# emonTx_V3_4.net
KiCad netlist of a schematic drawn in EAGLE
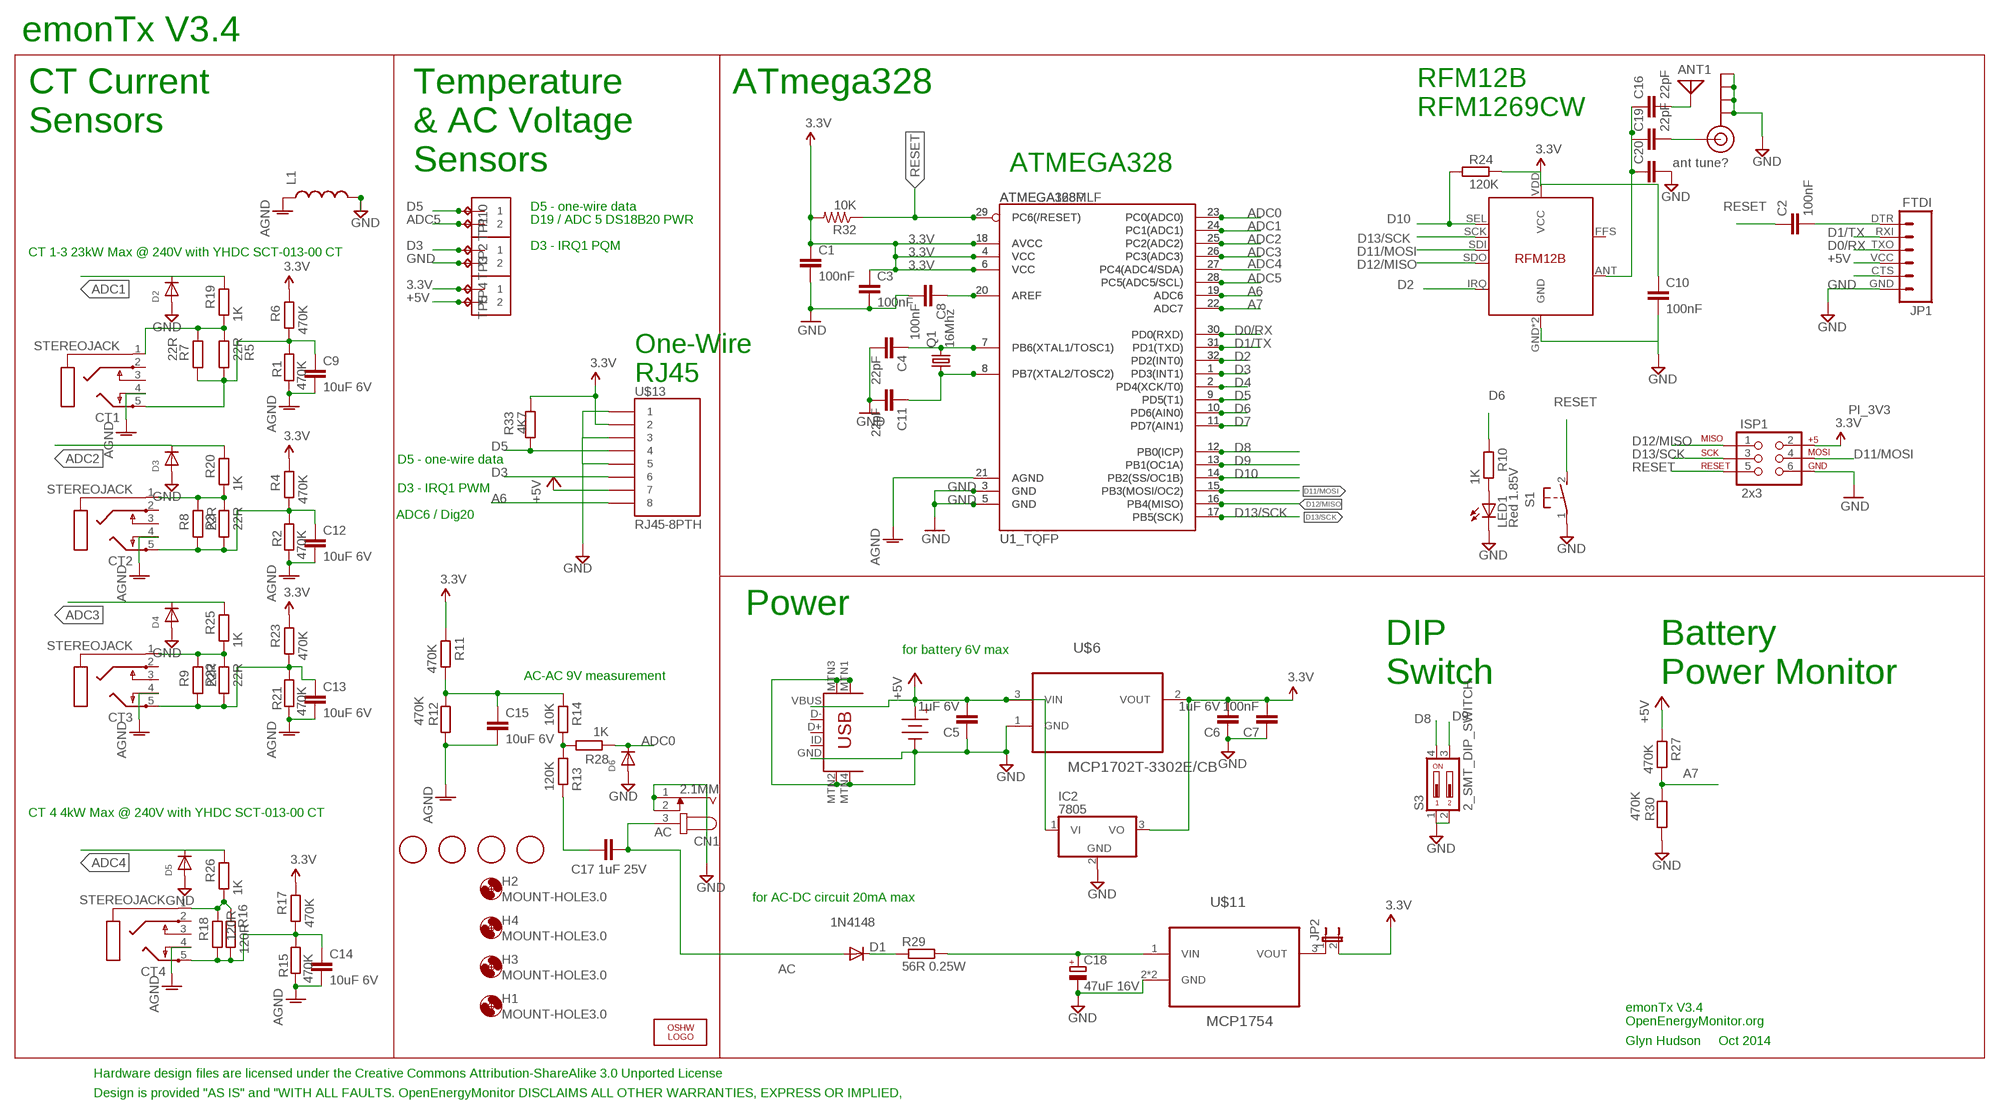
[diagram p0: schematic, sheet 1]

(export (version "E")
  (design (tool "Eeschema 10.0.6"))
  (components
    (comp (ref "ANT1")
      (value "ANTENNA")
      (footprint "eagle-import:PAD-01")
      (libsource (lib "eagle-import") (part "ANTENNA"))
    )
    (comp (ref "C1")
      (value "100nF")
      (footprint "eagle-import:C0603")
      (libsource (lib "eagle-import") (part "C-EUC0603"))
    )
    (comp (ref "C2")
      (value "100nF")
      (footprint "eagle-import:C0603")
      (libsource (lib "eagle-import") (part "C-EUC0603"))
    )
    (comp (ref "C3")
      (value "100nF")
      (footprint "eagle-import:C0603")
      (libsource (lib "eagle-import") (part "resistor_C-EUC0603"))
    )
    (comp (ref "C4")
      (value "22pF")
      (footprint "eagle-import:C0603")
      (libsource (lib "eagle-import") (part "resistor_C-EUC0603"))
    )
    (comp (ref "C5")
      (value "1uF 6V")
      (footprint "eagle-import:C0603")
      (libsource (lib "eagle-import") (part "resistor_C-EUC0603"))
    )
    (comp (ref "C6")
      (value "1uF 6V")
      (footprint "eagle-import:C0603")
      (libsource (lib "eagle-import") (part "resistor_C-EUC0603"))
    )
    (comp (ref "C7")
      (value "100nF")
      (footprint "eagle-import:C0603")
      (libsource (lib "eagle-import") (part "resistor_C-EUC0603"))
    )
    (comp (ref "C8")
      (value "100nF")
      (footprint "eagle-import:C0603")
      (libsource (lib "eagle-import") (part "resistor_C-EUC0603"))
    )
    (comp (ref "C9")
      (value "10uF 6V")
      (footprint "eagle-import:C0603")
      (libsource (lib "eagle-import") (part "resistor_C-EUC0603"))
    )
    (comp (ref "C10")
      (value "100nF")
      (footprint "eagle-import:C0603")
      (libsource (lib "eagle-import") (part "C-EUC0603"))
    )
    (comp (ref "C11")
      (value "22pF")
      (footprint "eagle-import:C0603")
      (libsource (lib "eagle-import") (part "resistor_C-EUC0603"))
    )
    (comp (ref "C12")
      (value "10uF 6V")
      (footprint "eagle-import:C0603")
      (libsource (lib "eagle-import") (part "resistor_C-EUC0603"))
    )
    (comp (ref "C13")
      (value "10uF 6V")
      (footprint "eagle-import:C0603")
      (libsource (lib "eagle-import") (part "resistor_C-EUC0603"))
    )
    (comp (ref "C14")
      (value "10uF 6V")
      (footprint "eagle-import:C0603")
      (libsource (lib "eagle-import") (part "resistor_C-EUC0603"))
    )
    (comp (ref "C15")
      (value "10uF 6V")
      (footprint "eagle-import:C0603")
      (libsource (lib "eagle-import") (part "resistor_C-EUC0603"))
    )
    (comp (ref "C16")
      (value "22pF")
      (footprint "eagle-import:C0603")
      (libsource (lib "eagle-import") (part "C-EUC0603"))
    )
    (comp (ref "C17")
      (value "1uF 25V")
      (footprint "eagle-import:C0603")
      (libsource (lib "eagle-import") (part "resistor_C-EUC0603"))
    )
    (comp (ref "C18")
      (value "47uF 16V")
      (footprint "eagle-import:PANASONIC_D")
      (libsource (lib "eagle-import") (part "CPOL-EUD"))
    )
    (comp (ref "C19")
      (value "22pF")
      (footprint "eagle-import:C0603")
      (libsource (lib "eagle-import") (part "C-EUC0603"))
    )
    (comp (ref "C20")
      (value "ant tune?")
      (footprint "eagle-import:C0603")
      (libsource (lib "eagle-import") (part "C-EUC0603"))
    )
    (comp (ref "CN1")
      (value "2.1MM")
      (footprint "eagle-import:SPC4077")
      (libsource (lib "eagle-import") (part "JACK-PLUG0"))
    )
    (comp (ref "CT1")
      (value "STEREOJACK")
      (footprint "eagle-import:STX3100")
      (libsource (lib "eagle-import") (part "STEREOJACK"))
    )
    (comp (ref "CT2")
      (value "STEREOJACK")
      (footprint "eagle-import:STX3100")
      (libsource (lib "eagle-import") (part "STEREOJACK"))
    )
    (comp (ref "CT3")
      (value "STEREOJACK")
      (footprint "eagle-import:STX3100")
      (libsource (lib "eagle-import") (part "STEREOJACK"))
    )
    (comp (ref "CT4")
      (value "STEREOJACK")
      (footprint "eagle-import:STX3100")
      (libsource (lib "eagle-import") (part "STEREOJACK"))
    )
    (comp (ref "D1")
      (value "1N4148")
      (footprint "eagle-import:SOD-323")
      (libsource (lib "eagle-import") (part "DIODESOD"))
    )
    (comp (ref "D2")
      (value "DIODESOD-523")
      (footprint "eagle-import:SOD-523")
      (libsource (lib "eagle-import") (part "DIODESOD-523"))
    )
    (comp (ref "D3")
      (value "DIODESOD-523")
      (footprint "eagle-import:SOD-523")
      (libsource (lib "eagle-import") (part "DIODESOD-523"))
    )
    (comp (ref "D4")
      (value "DIODESOD-523")
      (footprint "eagle-import:SOD-523")
      (libsource (lib "eagle-import") (part "DIODESOD-523"))
    )
    (comp (ref "D5")
      (value "DIODESOD-523")
      (footprint "eagle-import:SOD-523")
      (libsource (lib "eagle-import") (part "DIODESOD-523"))
    )
    (comp (ref "D6")
      (value "DIODESOD-523")
      (footprint "eagle-import:SOD-523")
      (libsource (lib "eagle-import") (part "DIODESOD-523"))
    )
    (comp (ref "H1")
      (value "MOUNT-HOLE3.0")
      (footprint "eagle-import:3,0")
      (libsource (lib "eagle-import") (part "MOUNT-HOLE3.0"))
    )
    (comp (ref "H2")
      (value "MOUNT-HOLE3.0")
      (footprint "eagle-import:3,0")
      (libsource (lib "eagle-import") (part "MOUNT-HOLE3.0"))
    )
    (comp (ref "H3")
      (value "MOUNT-HOLE3.0")
      (footprint "eagle-import:3,0")
      (libsource (lib "eagle-import") (part "MOUNT-HOLE3.0"))
    )
    (comp (ref "H4")
      (value "MOUNT-HOLE3.0")
      (footprint "eagle-import:3,0")
      (libsource (lib "eagle-import") (part "MOUNT-HOLE3.0"))
    )
    (comp (ref "IC2")
      (value "7805")
      (footprint "eagle-import:TO220V")
      (libsource (lib "eagle-import") (part "78TV12"))
    )
    (comp (ref "ISP1")
      (value "2x3")
      (footprint "eagle-import:2X3")
      (libsource (lib "eagle-import") (part "AVR_SPI_PRG_6PTH"))
    )
    (comp (ref "J$1")
      (value "SMA_EDGE")
      (footprint "eagle-import:SMA-EDGE")
      (libsource (lib "eagle-import") (part "SMA_EDGE"))
    )
    (comp (ref "J3")
      (value "1X2-3.5MM")
      (footprint "eagle-import:1X2-3.5MM")
      (libsource (lib "eagle-import") (part "1X2-3.5MM"))
    )
    (comp (ref "J5")
      (value "1X2-3.5MM")
      (footprint "eagle-import:1X2-3.5MM")
      (libsource (lib "eagle-import") (part "1X2-3.5MM"))
    )
    (comp (ref "J6")
      (value "1X2-3.5MM")
      (footprint "eagle-import:1X2-3.5MM")
      (libsource (lib "eagle-import") (part "1X2-3.5MM"))
    )
    (comp (ref "JP1")
      (value "FTDI")
      (footprint "eagle-import:FTDI_BASIC")
      (libsource (lib "eagle-import") (part "FTDI_BASICPTH"))
    )
    (comp (ref "JP2")
      (value "JUMPER-2PTH_LOCK")
      (footprint "eagle-import:1X02_LOCK")
      (libsource (lib "eagle-import") (part "JUMPER-2PTH_LOCK"))
    )
    (comp (ref "L1")
      (value "INDUCTOR0603")
      (footprint "eagle-import:0603")
      (libsource (lib "eagle-import") (part "INDUCTOR0603"))
    )
    (comp (ref "LED1")
      (value "Red 1.85V")
      (footprint "eagle-import:CHIP-LED0805")
      (libsource (lib "eagle-import") (part "LEDCHIP-LED0805"))
    )
    (comp (ref "LOGO1")
      (value "OSHW_LOGO_6MILX0200-NT")
      (footprint "eagle-import:OSHW_6X200_NOTEXT")
      (libsource (lib "eagle-import") (part "OSHW_LOGO_6MILX0200-NT"))
    )
    (comp (ref "Q1")
      (value "16Mhz")
      (footprint "eagle-import:HC49UP")
      (libsource (lib "eagle-import") (part "CRYSTALHC49UP"))
    )
    (comp (ref "R1")
      (value "470K")
      (footprint "eagle-import:R0603")
      (libsource (lib "eagle-import") (part "R-EU_R0603"))
    )
    (comp (ref "R2")
      (value "470K")
      (footprint "eagle-import:R0603")
      (libsource (lib "eagle-import") (part "R-EU_R0603"))
    )
    (comp (ref "R3")
      (value "22R")
      (footprint "eagle-import:0204_7")
      (libsource (lib "eagle-import") (part "R-EU_0204/7"))
    )
    (comp (ref "R4")
      (value "470K")
      (footprint "eagle-import:R0603")
      (libsource (lib "eagle-import") (part "R-EU_R0603"))
    )
    (comp (ref "R5")
      (value "22R")
      (footprint "eagle-import:0204_7")
      (libsource (lib "eagle-import") (part "R-EU_0204/7"))
    )
    (comp (ref "R6")
      (value "470K")
      (footprint "eagle-import:R0603")
      (libsource (lib "eagle-import") (part "R-EU_R0603"))
    )
    (comp (ref "R7")
      (value "22R")
      (footprint "eagle-import:R1206")
      (libsource (lib "eagle-import") (part "R-EU_R1206"))
    )
    (comp (ref "R8")
      (value "22R")
      (footprint "eagle-import:R1206")
      (libsource (lib "eagle-import") (part "R-EU_R1206"))
    )
    (comp (ref "R9")
      (value "22R")
      (footprint "eagle-import:R1206")
      (libsource (lib "eagle-import") (part "R-EU_R1206"))
    )
    (comp (ref "R10")
      (value "1K")
      (footprint "eagle-import:R0603")
      (libsource (lib "eagle-import") (part "R-EU_R0603"))
    )
    (comp (ref "R11")
      (value "470K")
      (footprint "eagle-import:R0603")
      (libsource (lib "eagle-import") (part "R-EU_R0603"))
    )
    (comp (ref "R12")
      (value "470K")
      (footprint "eagle-import:R0603")
      (libsource (lib "eagle-import") (part "R-EU_R0603"))
    )
    (comp (ref "R13")
      (value "120K")
      (footprint "eagle-import:R0603")
      (libsource (lib "eagle-import") (part "R-EU_R0603"))
    )
    (comp (ref "R14")
      (value "10K")
      (footprint "eagle-import:R0603")
      (libsource (lib "eagle-import") (part "R-EU_R0603"))
    )
    (comp (ref "R15")
      (value "470K")
      (footprint "eagle-import:R0603")
      (libsource (lib "eagle-import") (part "R-EU_R0603"))
    )
    (comp (ref "R16")
      (value "120R")
      (footprint "eagle-import:0204_7")
      (libsource (lib "eagle-import") (part "R-EU_0204/7"))
    )
    (comp (ref "R17")
      (value "470K")
      (footprint "eagle-import:R0603")
      (libsource (lib "eagle-import") (part "R-EU_R0603"))
    )
    (comp (ref "R18")
      (value "120R")
      (footprint "eagle-import:R1206")
      (libsource (lib "eagle-import") (part "R-EU_R1206"))
    )
    (comp (ref "R19")
      (value "1K")
      (footprint "eagle-import:R0603")
      (libsource (lib "eagle-import") (part "R-EU_R0603"))
    )
    (comp (ref "R20")
      (value "1K")
      (footprint "eagle-import:R0603")
      (libsource (lib "eagle-import") (part "R-EU_R0603"))
    )
    (comp (ref "R21")
      (value "470K")
      (footprint "eagle-import:R0603")
      (libsource (lib "eagle-import") (part "R-EU_R0603"))
    )
    (comp (ref "R22")
      (value "22R")
      (footprint "eagle-import:0204_7")
      (libsource (lib "eagle-import") (part "R-EU_0204/7"))
    )
    (comp (ref "R23")
      (value "470K")
      (footprint "eagle-import:R0603")
      (libsource (lib "eagle-import") (part "R-EU_R0603"))
    )
    (comp (ref "R24")
      (value "120K")
      (footprint "eagle-import:R0603")
      (libsource (lib "eagle-import") (part "R-EU_R0603"))
    )
    (comp (ref "R25")
      (value "1K")
      (footprint "eagle-import:R0603")
      (libsource (lib "eagle-import") (part "R-EU_R0603"))
    )
    (comp (ref "R26")
      (value "1K")
      (footprint "eagle-import:R0603")
      (libsource (lib "eagle-import") (part "R-EU_R0603"))
    )
    (comp (ref "R27")
      (value "470K")
      (footprint "eagle-import:R0603")
      (libsource (lib "eagle-import") (part "R-EU_R0603"))
    )
    (comp (ref "R28")
      (value "1K")
      (footprint "eagle-import:R0603")
      (libsource (lib "eagle-import") (part "R-EU_R0603"))
    )
    (comp (ref "R29")
      (value "56R 0.25W")
      (footprint "eagle-import:R1206")
      (libsource (lib "eagle-import") (part "resistor_R-EU_R1206"))
    )
    (comp (ref "R30")
      (value "470K")
      (footprint "eagle-import:R0603")
      (libsource (lib "eagle-import") (part "R-EU_R0603"))
    )
    (comp (ref "R32")
      (value "10K")
      (footprint "eagle-import:R0603")
      (libsource (lib "eagle-import") (part "R-US_R0603"))
    )
    (comp (ref "R33")
      (value "4K7")
      (footprint "eagle-import:R0603")
      (libsource (lib "eagle-import") (part "R-EU_R0603"))
    )
    (comp (ref "S1")
      (value "31-XX")
      (footprint "eagle-import:B3F-31XX")
      (libsource (lib "eagle-import") (part "31-XX"))
    )
    (comp (ref "S3")
      (value "2_SMT_DIP_SWITCH")
      (footprint "eagle-import:DIP_SWITCH_SMT")
      (libsource (lib "eagle-import") (part "2_SMT_DIP_SWITCH"))
    )
    (comp (ref "TP1")
      (value "TPPAD1-13")
      (footprint "eagle-import:P1-13")
      (libsource (lib "eagle-import") (part "TPPAD1-13"))
    )
    (comp (ref "TP2")
      (value "TPPAD1-13")
      (footprint "eagle-import:P1-13")
      (libsource (lib "eagle-import") (part "TPPAD1-13"))
    )
    (comp (ref "TP3")
      (value "TPPAD1-13")
      (footprint "eagle-import:P1-13")
      (libsource (lib "eagle-import") (part "TPPAD1-13"))
    )
    (comp (ref "TP4")
      (value "TPPAD1-13")
      (footprint "eagle-import:P1-13")
      (libsource (lib "eagle-import") (part "TPPAD1-13"))
    )
    (comp (ref "TP5")
      (value "TPPAD1-13")
      (footprint "eagle-import:P1-13")
      (libsource (lib "eagle-import") (part "TPPAD1-13"))
    )
    (comp (ref "TP10")
      (value "TPPAD1-13")
      (footprint "eagle-import:P1-13")
      (libsource (lib "eagle-import") (part "TPPAD1-13"))
    )
    (comp (ref "U$1")
      (value "FIDUCIAL")
      (footprint "eagle-import:FIDUCIAL_1MM")
      (libsource (lib "eagle-import") (part "FIDUCIAL"))
    )
    (comp (ref "U$3")
      (value "4.5V")
      (footprint "eagle-import:AAA_PCB_HOLDER")
      (libsource (lib "eagle-import") (part "3X_AAA_BATTERY_HOLDER"))
    )
    (comp (ref "U$4")
      (value "FIDUCIAL")
      (footprint "eagle-import:FIDUCIAL_1MM")
      (libsource (lib "eagle-import") (part "FIDUCIAL"))
    )
    (comp (ref "U$5")
      (value "FIDUCIAL")
      (footprint "eagle-import:FIDUCIAL_1MM")
      (libsource (lib "eagle-import") (part "FIDUCIAL"))
    )
    (comp (ref "U$6")
      (value "MCP1702T-3302E/CB")
      (footprint "eagle-import:SOT95P237X112-3N")
      (fields (field (name "MPN") "MCP1700T-3302E/TT"))
      (libsource (lib "eagle-import") (part "MCP1700T-3302E/TT"))
    )
    (comp (ref "U$7")
      (value "FIDUCIAL")
      (footprint "eagle-import:FIDUCIAL_1MM")
      (libsource (lib "eagle-import") (part "FIDUCIAL"))
    )
    (comp (ref "U$10")
      (value "USB-MINIB-5PIN")
      (footprint "eagle-import:USB-MINIB-CISECO")
      (libsource (lib "eagle-import") (part "USB-MINIB-5PIN"))
    )
    (comp (ref "U$11")
      (value "MCP1754")
      (footprint "eagle-import:SOT89")
      (libsource (lib "eagle-import") (part "MCP1754"))
    )
    (comp (ref "U$13")
      (value "RJ45-8PTH")
      (footprint "eagle-import:RJ45-8")
      (libsource (lib "eagle-import") (part "RJ45-8PTH"))
    )
    (comp (ref "U$14")
      (value "RFM12B")
      (footprint "eagle-import:RFM12B")
      (libsource (lib "eagle-import") (part "RFM12B"))
    )
    (comp (ref "U1")
      (value "ATMEGA168MLF")
      (footprint "eagle-import:MLF32")
      (libsource (lib "eagle-import") (part "ATMEGA168MLF"))
    )
    (comp (ref "U1_TQFP")
      (value "ATMEGA328P")
      (footprint "eagle-import:TQFP32-08")
      (libsource (lib "eagle-import") (part "ATMEGA328_SMT"))
    )
  )
  (nets
    (net (code "1") (name "+5V") (class "Default")
      (node (ref "C5") (pin "2") (pinfunction "2_2") (pintype "passive"))
      (node (ref "IC2") (pin "1") (pinfunction "VI_1") (pintype "input"))
      (node (ref "J6") (pin "2") (pinfunction "2_2") (pintype "passive"))
      (node (ref "JP1") (pin "VCC") (pinfunction "4_VCC") (pintype "passive"))
      (node (ref "R27") (pin "2") (pinfunction "2_2") (pintype "passive"))
      (node (ref "TP5") (pin "TP") (pinfunction "TP_TP") (pintype "input"))
      (node (ref "U$10") (pin "VBUS") (pinfunction "VBUS_VBUS") (pintype "bidirectional"))
      (node (ref "U$13") (pin "7") (pinfunction "7_7") (pintype "bidirectional"))
      (node (ref "U$3") (pin "+") (pinfunction "+_+") (pintype "power_in"))
      (node (ref "U$6") (pin "3") (pinfunction "VIN_3") (pintype "input"))
    )
    (net (code "2") (name "/A6") (class "Default")
      (node (ref "U$13") (pin "8") (pinfunction "8_8") (pintype "bidirectional"))
      (node (ref "U1") (pin "19") (pinfunction "ADC6_19") (pintype "bidirectional"))
      (node (ref "U1_TQFP") (pin "19") (pinfunction "ADC6_19") (pintype "bidirectional"))
    )
    (net (code "3") (name "/A7") (class "Default")
      (node (ref "R27") (pin "1") (pinfunction "1_1") (pintype "passive"))
      (node (ref "R30") (pin "2") (pinfunction "2_2") (pintype "passive"))
      (node (ref "U1") (pin "22") (pinfunction "ADC7_22") (pintype "bidirectional"))
      (node (ref "U1_TQFP") (pin "22") (pinfunction "ADC7_22") (pintype "bidirectional"))
    )
    (net (code "4") (name "/AC") (class "Default")
      (node (ref "C17") (pin "2") (pinfunction "2_2") (pintype "passive"))
      (node (ref "CN1") (pin "3") (pinfunction "3_3") (pintype "passive"))
      (node (ref "D1") (pin "2") (pinfunction "A_2") (pintype "passive"))
    )
    (net (code "5") (name "/ADC0") (class "Default")
      (node (ref "D6") (pin "K") (pinfunction "C_K") (pintype "passive"))
      (node (ref "R28") (pin "1") (pinfunction "1_1") (pintype "passive"))
      (node (ref "U1") (pin "23") (pinfunction "PC0(ADC0)_23") (pintype "bidirectional"))
      (node (ref "U1_TQFP") (pin "23") (pinfunction "PC0(ADC0)_23") (pintype "bidirectional"))
    )
    (net (code "6") (name "/ADC5") (class "Default")
      (node (ref "J3") (pin "2") (pinfunction "2_2") (pintype "passive"))
      (node (ref "TP1") (pin "TP") (pinfunction "TP_TP") (pintype "input"))
      (node (ref "U1") (pin "28") (pinfunction "PC5(ADC5/SCL)_28") (pintype "bidirectional"))
      (node (ref "U1_TQFP") (pin "28") (pinfunction "PC5(ADC5/SCL)_28") (pintype "bidirectional"))
    )
    (net (code "7") (name "/D0{slash}RX") (class "Default")
      (node (ref "JP1") (pin "TXO") (pinfunction "3_TXO") (pintype "passive"))
      (node (ref "U1") (pin "30") (pinfunction "PD0(RXD)_30") (pintype "bidirectional"))
      (node (ref "U1_TQFP") (pin "30") (pinfunction "PD0(RXD)_30") (pintype "bidirectional"))
    )
    (net (code "8") (name "/D1{slash}TX") (class "Default")
      (node (ref "JP1") (pin "RXI") (pinfunction "2_RXI") (pintype "passive"))
      (node (ref "U1") (pin "31") (pinfunction "PD1(TXD)_31") (pintype "bidirectional"))
      (node (ref "U1_TQFP") (pin "31") (pinfunction "PD1(TXD)_31") (pintype "bidirectional"))
    )
    (net (code "9") (name "/D2") (class "Default")
      (node (ref "U$14") (pin "IRQ") (pinfunction "IRQ_IRQ") (pintype "open_collector"))
      (node (ref "U1") (pin "32") (pinfunction "PD2(INT0)_32") (pintype "bidirectional"))
      (node (ref "U1_TQFP") (pin "32") (pinfunction "PD2(INT0)_32") (pintype "bidirectional"))
    )
    (net (code "10") (name "/D3") (class "Default")
      (node (ref "J5") (pin "1") (pinfunction "1_1") (pintype "passive"))
      (node (ref "TP2") (pin "TP") (pinfunction "TP_TP") (pintype "input"))
      (node (ref "U$13") (pin "6") (pinfunction "6_6") (pintype "bidirectional"))
      (node (ref "U1") (pin "1") (pinfunction "PD3(INT1)_1") (pintype "bidirectional"))
      (node (ref "U1_TQFP") (pin "1") (pinfunction "PD3(INT1)_1") (pintype "bidirectional"))
    )
    (net (code "11") (name "/D4") (class "Default")
      (node (ref "U1") (pin "2") (pinfunction "PD4(XCK/T0)_2") (pintype "bidirectional"))
      (node (ref "U1_TQFP") (pin "2") (pinfunction "PD4(XCK/T0)_2") (pintype "bidirectional"))
    )
    (net (code "12") (name "/D5") (class "Default")
      (node (ref "J3") (pin "1") (pinfunction "1_1") (pintype "passive"))
      (node (ref "R33") (pin "2") (pinfunction "2_2") (pintype "passive"))
      (node (ref "TP10") (pin "TP") (pinfunction "TP_TP") (pintype "input"))
      (node (ref "U$13") (pin "4") (pinfunction "4_4") (pintype "bidirectional"))
      (node (ref "U1") (pin "9") (pinfunction "PD5(T1)_9") (pintype "bidirectional"))
      (node (ref "U1_TQFP") (pin "9") (pinfunction "PD5(T1)_9") (pintype "bidirectional"))
    )
    (net (code "13") (name "/D6") (class "Default")
      (node (ref "R10") (pin "2") (pinfunction "2_2") (pintype "passive"))
      (node (ref "U1") (pin "10") (pinfunction "PD6(AIN0)_10") (pintype "bidirectional"))
      (node (ref "U1_TQFP") (pin "10") (pinfunction "PD6(AIN0)_10") (pintype "bidirectional"))
    )
    (net (code "14") (name "/D7") (class "Default")
      (node (ref "U1") (pin "11") (pinfunction "PD7(AIN1)_11") (pintype "bidirectional"))
      (node (ref "U1_TQFP") (pin "11") (pinfunction "PD7(AIN1)_11") (pintype "bidirectional"))
    )
    (net (code "15") (name "/D8") (class "Default")
      (node (ref "S3") (pin "4") (pinfunction "4_4") (pintype "passive"))
      (node (ref "U1") (pin "12") (pinfunction "PB0(ICP)_12") (pintype "bidirectional"))
      (node (ref "U1_TQFP") (pin "12") (pinfunction "PB0(ICP)_12") (pintype "bidirectional"))
    )
    (net (code "16") (name "/D9") (class "Default")
      (node (ref "S3") (pin "3") (pinfunction "3_3") (pintype "passive"))
      (node (ref "U1") (pin "13") (pinfunction "PB1(OC1A)_13") (pintype "bidirectional"))
      (node (ref "U1_TQFP") (pin "13") (pinfunction "PB1(OC1A)_13") (pintype "bidirectional"))
    )
    (net (code "17") (name "/D10") (class "Default")
      (node (ref "R24") (pin "1") (pinfunction "1_1") (pintype "passive"))
      (node (ref "U$14") (pin "SEL") (pinfunction "SEL_SEL") (pintype "input"))
      (node (ref "U1") (pin "14") (pinfunction "PB2(SS/OC1B)_14") (pintype "bidirectional"))
      (node (ref "U1_TQFP") (pin "14") (pinfunction "PB2(SS/OC1B)_14") (pintype "bidirectional"))
    )
    (net (code "19") (name "3.3V") (class "Default")
      (node (ref "C1") (pin "1") (pinfunction "1_1") (pintype "passive"))
      (node (ref "C10") (pin "1") (pinfunction "1_1") (pintype "passive"))
      (node (ref "C3") (pin "1") (pinfunction "1_1") (pintype "passive"))
      (node (ref "C6") (pin "2") (pinfunction "2_2") (pintype "passive"))
      (node (ref "C7") (pin "2") (pinfunction "2_2") (pintype "passive"))
      (node (ref "IC2") (pin "3") (pinfunction "VO_3") (pintype "passive"))
      (node (ref "ISP1") (pin "2") (pinfunction "2_2") (pintype "passive"))
      (node (ref "J6") (pin "1") (pinfunction "1_1") (pintype "passive"))
      (node (ref "JP2") (pin "2") (pinfunction "2_2") (pintype "passive"))
      (node (ref "R11") (pin "2") (pinfunction "2_2") (pintype "passive"))
      (node (ref "R17") (pin "2") (pinfunction "2_2") (pintype "passive"))
      (node (ref "R23") (pin "2") (pinfunction "2_2") (pintype "passive"))
      (node (ref "R24") (pin "2") (pinfunction "2_2") (pintype "passive"))
      (node (ref "R32") (pin "2") (pinfunction "2_2") (pintype "passive"))
      (node (ref "R33") (pin "1") (pinfunction "1_1") (pintype "passive"))
      (node (ref "R4") (pin "2") (pinfunction "2_2") (pintype "passive"))
      (node (ref "R6") (pin "2") (pinfunction "2_2") (pintype "passive"))
      (node (ref "TP4") (pin "TP") (pinfunction "TP_TP") (pintype "input"))
      (node (ref "U$13") (pin "2") (pinfunction "2_2") (pintype "bidirectional"))
      (node (ref "U$14") (pin "VDD") (pinfunction "VCC_VDD") (pintype "power_in"))
      (node (ref "U$6") (pin "2") (pinfunction "VOUT_2") (pintype "output"))
      (node (ref "U1") (pin "18") (pinfunction "AVCC_18") (pintype "bidirectional"))
      (node (ref "U1") (pin "4") (pinfunction "VCC_4") (pintype "bidirectional"))
      (node (ref "U1") (pin "6") (pinfunction "VCC_6") (pintype "bidirectional"))
      (node (ref "U1_TQFP") (pin "18") (pinfunction "AVCC_18") (pintype "bidirectional"))
      (node (ref "U1_TQFP") (pin "4") (pinfunction "VCC_4") (pintype "bidirectional"))
      (node (ref "U1_TQFP") (pin "6") (pinfunction "VCC_6") (pintype "bidirectional"))
    )
    (net (code "20") (name "ADC1") (class "Default")
      (node (ref "D2") (pin "K") (pinfunction "C_K") (pintype "passive"))
      (node (ref "R19") (pin "2") (pinfunction "2_2") (pintype "passive"))
      (node (ref "U1") (pin "24") (pinfunction "PC1(ADC1)_24") (pintype "bidirectional"))
      (node (ref "U1_TQFP") (pin "24") (pinfunction "PC1(ADC1)_24") (pintype "bidirectional"))
    )
    (net (code "21") (name "ADC2") (class "Default")
      (node (ref "D3") (pin "K") (pinfunction "C_K") (pintype "passive"))
      (node (ref "R20") (pin "2") (pinfunction "2_2") (pintype "passive"))
      (node (ref "U1") (pin "25") (pinfunction "PC2(ADC2)_25") (pintype "bidirectional"))
      (node (ref "U1_TQFP") (pin "25") (pinfunction "PC2(ADC2)_25") (pintype "bidirectional"))
    )
    (net (code "22") (name "ADC3") (class "Default")
      (node (ref "D4") (pin "K") (pinfunction "C_K") (pintype "passive"))
      (node (ref "R25") (pin "2") (pinfunction "2_2") (pintype "passive"))
      (node (ref "U1") (pin "26") (pinfunction "PC3(ADC3)_26") (pintype "bidirectional"))
      (node (ref "U1_TQFP") (pin "26") (pinfunction "PC3(ADC3)_26") (pintype "bidirectional"))
    )
    (net (code "23") (name "ADC4") (class "Default")
      (node (ref "D5") (pin "K") (pinfunction "C_K") (pintype "passive"))
      (node (ref "R26") (pin "2") (pinfunction "2_2") (pintype "passive"))
      (node (ref "U1") (pin "27") (pinfunction "PC4(ADC4/SDA)_27") (pintype "bidirectional"))
      (node (ref "U1_TQFP") (pin "27") (pinfunction "PC4(ADC4/SDA)_27") (pintype "bidirectional"))
    )
    (net (code "24") (name "AGND") (class "Default")
      (node (ref "C12") (pin "2") (pinfunction "2_2") (pintype "passive"))
      (node (ref "C13") (pin "2") (pinfunction "2_2") (pintype "passive"))
      (node (ref "C14") (pin "2") (pinfunction "2_2") (pintype "passive"))
      (node (ref "C15") (pin "2") (pinfunction "2_2") (pintype "passive"))
      (node (ref "C9") (pin "2") (pinfunction "2_2") (pintype "passive"))
      (node (ref "CT1") (pin "4") (pinfunction "4_4") (pintype "passive"))
      (node (ref "CT2") (pin "4") (pinfunction "4_4") (pintype "passive"))
      (node (ref "CT3") (pin "4") (pinfunction "4_4") (pintype "passive"))
      (node (ref "CT4") (pin "4") (pinfunction "4_4") (pintype "passive"))
      (node (ref "L1") (pin "1") (pinfunction "1_1") (pintype "passive"))
      (node (ref "R1") (pin "2") (pinfunction "2_2") (pintype "passive"))
      (node (ref "R12") (pin "1") (pinfunction "1_1") (pintype "passive"))
      (node (ref "R15") (pin "2") (pinfunction "2_2") (pintype "passive"))
      (node (ref "R2") (pin "2") (pinfunction "2_2") (pintype "passive"))
      (node (ref "R21") (pin "2") (pinfunction "2_2") (pintype "passive"))
      (node (ref "U1") (pin "21") (pinfunction "AGND_21") (pintype "bidirectional"))
      (node (ref "U1_TQFP") (pin "21") (pinfunction "AGND_21") (pintype "bidirectional"))
    )
    (net (code "25") (name "D11{slash}MOSI") (class "Default")
      (node (ref "ISP1") (pin "4") (pinfunction "4_4") (pintype "passive"))
      (node (ref "U$14") (pin "SDI") (pinfunction "SDI_SDI") (pintype "input"))
      (node (ref "U1") (pin "15") (pinfunction "PB3(MOSI/OC2)_15") (pintype "bidirectional"))
      (node (ref "U1_TQFP") (pin "15") (pinfunction "PB3(MOSI/OC2)_15") (pintype "bidirectional"))
    )
    (net (code "26") (name "D12{slash}MISO") (class "Default")
      (node (ref "ISP1") (pin "1") (pinfunction "1_1") (pintype "passive"))
      (node (ref "U$14") (pin "SDO") (pinfunction "SDO_SDO") (pintype "output"))
      (node (ref "U1") (pin "16") (pinfunction "PB4(MISO)_16") (pintype "bidirectional"))
      (node (ref "U1_TQFP") (pin "16") (pinfunction "PB4(MISO)_16") (pintype "bidirectional"))
    )
    (net (code "27") (name "D13{slash}SCK") (class "Default")
      (node (ref "ISP1") (pin "3") (pinfunction "3_3") (pintype "passive"))
      (node (ref "U$14") (pin "SCK") (pinfunction "SCK_SCK") (pintype "input"))
      (node (ref "U1") (pin "17") (pinfunction "PB5(SCK)_17") (pintype "bidirectional"))
      (node (ref "U1_TQFP") (pin "17") (pinfunction "PB5(SCK)_17") (pintype "bidirectional"))
    )
    (net (code "28") (name "GND") (class "Default")
      (node (ref "C1") (pin "2") (pinfunction "2_2") (pintype "passive"))
      (node (ref "C10") (pin "2") (pinfunction "2_2") (pintype "passive"))
      (node (ref "C11") (pin "2") (pinfunction "2_2") (pintype "passive"))
      (node (ref "C18") (pin "-") (pinfunction "-_-") (pintype "passive"))
      (node (ref "C20") (pin "2") (pinfunction "2_2") (pintype "passive"))
      (node (ref "C3") (pin "2") (pinfunction "2_2") (pintype "passive"))
      (node (ref "C4") (pin "2") (pinfunction "2_2") (pintype "passive"))
      (node (ref "C5") (pin "1") (pinfunction "1_1") (pintype "passive"))
      (node (ref "C6") (pin "1") (pinfunction "1_1") (pintype "passive"))
      (node (ref "C7") (pin "1") (pinfunction "1_1") (pintype "passive"))
      (node (ref "C8") (pin "2") (pinfunction "2_2") (pintype "passive"))
      (node (ref "CN1") (pin "1") (pinfunction "1_1") (pintype "passive"))
      (node (ref "CN1") (pin "2") (pinfunction "2_2") (pintype "passive"))
      (node (ref "D2") (pin "A") (pinfunction "A_A") (pintype "passive"))
      (node (ref "D3") (pin "A") (pinfunction "A_A") (pintype "passive"))
      (node (ref "D4") (pin "A") (pinfunction "A_A") (pintype "passive"))
      (node (ref "D5") (pin "A") (pinfunction "A_A") (pintype "passive"))
      (node (ref "D6") (pin "A") (pinfunction "A_A") (pintype "passive"))
      (node (ref "IC2") (pin "2") (pinfunction "GND_2") (pintype "passive"))
      (node (ref "ISP1") (pin "6") (pinfunction "6_6") (pintype "passive"))
      (node (ref "J$1") (pin "GND@0") (pinfunction "GND_GND@0") (pintype "bidirectional"))
      (node (ref "J$1") (pin "GND@1") (pinfunction "GND_GND@1") (pintype "bidirectional"))
      (node (ref "J$1") (pin "GND@2") (pinfunction "GND_GND@2") (pintype "bidirectional"))
      (node (ref "J$1") (pin "GND@3") (pinfunction "GND_GND@3") (pintype "bidirectional"))
      (node (ref "J5") (pin "2") (pinfunction "2_2") (pintype "passive"))
      (node (ref "JP1") (pin "GND") (pinfunction "6_GND") (pintype "passive"))
      (node (ref "L1") (pin "2") (pinfunction "2_2") (pintype "passive"))
      (node (ref "LED1") (pin "C") (pinfunction "C_C") (pintype "passive"))
      (node (ref "R30") (pin "1") (pinfunction "1_1") (pintype "passive"))
      (node (ref "S1") (pin "1") (pinfunction "P_1") (pintype "passive"))
      (node (ref "S3") (pin "1") (pinfunction "1_1") (pintype "passive"))
      (node (ref "S3") (pin "2") (pinfunction "2_2") (pintype "passive"))
      (node (ref "TP3") (pin "TP") (pinfunction "TP_TP") (pintype "input"))
      (node (ref "U$10") (pin "GND") (pinfunction "GND_GND") (pintype "bidirectional"))
      (node (ref "U$10") (pin "MTN1") (pinfunction "MTN2_MTN1") (pintype "bidirectional"))
      (node (ref "U$10") (pin "MTN2") (pinfunction "MTN3_MTN2") (pintype "bidirectional"))
      (node (ref "U$10") (pin "MTN3") (pinfunction "MTN1_MTN3") (pintype "bidirectional"))
      (node (ref "U$10") (pin "MTN4") (pinfunction "MTN4_MTN4") (pintype "bidirectional"))
      (node (ref "U$11") (pin "2") (pinfunction "GND_2") (pintype "passive"))
      (node (ref "U$11") (pin "2.1") (pinfunction "GND_2.1") (pintype "passive"))
      (node (ref "U$13") (pin "1") (pinfunction "1_1") (pintype "bidirectional"))
      (node (ref "U$13") (pin "3") (pinfunction "3_3") (pintype "bidirectional"))
      (node (ref "U$13") (pin "5") (pinfunction "5_5") (pintype "bidirectional"))
      (node (ref "U$14") (pin "GND") (pinfunction "GND_GND") (pintype "power_in"))
      (node (ref "U$14") (pin "P$12") (pinfunction "GND_P$12") (pintype "power_in"))
      (node (ref "U$3") (pin "-") (pinfunction "-_-") (pintype "power_in"))
      (node (ref "U$6") (pin "1") (pinfunction "GND_1") (pintype "passive"))
      (node (ref "U1") (pin "3") (pinfunction "GND_3") (pintype "bidirectional"))
      (node (ref "U1") (pin "5") (pinfunction "GND_5") (pintype "bidirectional"))
      (node (ref "U1_TQFP") (pin "3") (pinfunction "GND_3") (pintype "bidirectional"))
      (node (ref "U1_TQFP") (pin "5") (pinfunction "GND_5") (pintype "bidirectional"))
    )
    (net (code "29") (name "Net-(ANT1-Pad1)") (class "Default")
      (node (ref "ANT1") (pin "1") (pinfunction "1_1") (pintype "output"))
      (node (ref "C16") (pin "2") (pinfunction "2_2") (pintype "passive"))
    )
    (net (code "30") (name "Net-(C9-Pad1)") (class "Default")
      (node (ref "C9") (pin "1") (pinfunction "1_1") (pintype "passive"))
      (node (ref "CT1") (pin "5") (pinfunction "5_5") (pintype "passive"))
      (node (ref "R1") (pin "1") (pinfunction "1_1") (pintype "passive"))
      (node (ref "R5") (pin "1") (pinfunction "1_1") (pintype "passive"))
      (node (ref "R6") (pin "1") (pinfunction "1_1") (pintype "passive"))
      (node (ref "R7") (pin "1") (pinfunction "1_1") (pintype "passive"))
    )
    (net (code "31") (name "Net-(C12-Pad1)") (class "Default")
      (node (ref "C12") (pin "1") (pinfunction "1_1") (pintype "passive"))
      (node (ref "CT2") (pin "5") (pinfunction "5_5") (pintype "passive"))
      (node (ref "R2") (pin "1") (pinfunction "1_1") (pintype "passive"))
      (node (ref "R3") (pin "1") (pinfunction "1_1") (pintype "passive"))
      (node (ref "R4") (pin "1") (pinfunction "1_1") (pintype "passive"))
      (node (ref "R8") (pin "1") (pinfunction "1_1") (pintype "passive"))
    )
    (net (code "32") (name "Net-(C13-Pad1)") (class "Default")
      (node (ref "C13") (pin "1") (pinfunction "1_1") (pintype "passive"))
      (node (ref "CT3") (pin "5") (pinfunction "5_5") (pintype "passive"))
      (node (ref "R21") (pin "1") (pinfunction "1_1") (pintype "passive"))
      (node (ref "R22") (pin "1") (pinfunction "1_1") (pintype "passive"))
      (node (ref "R23") (pin "1") (pinfunction "1_1") (pintype "passive"))
      (node (ref "R9") (pin "1") (pinfunction "1_1") (pintype "passive"))
    )
    (net (code "33") (name "Net-(C14-Pad1)") (class "Default")
      (node (ref "C14") (pin "1") (pinfunction "1_1") (pintype "passive"))
      (node (ref "CT4") (pin "5") (pinfunction "5_5") (pintype "passive"))
      (node (ref "R15") (pin "1") (pinfunction "1_1") (pintype "passive"))
      (node (ref "R16") (pin "1") (pinfunction "1_1") (pintype "passive"))
      (node (ref "R17") (pin "1") (pinfunction "1_1") (pintype "passive"))
      (node (ref "R18") (pin "1") (pinfunction "1_1") (pintype "passive"))
    )
    (net (code "34") (name "Net-(C15-Pad1)") (class "Default")
      (node (ref "C15") (pin "1") (pinfunction "1_1") (pintype "passive"))
      (node (ref "R11") (pin "1") (pinfunction "1_1") (pintype "passive"))
      (node (ref "R12") (pin "2") (pinfunction "2_2") (pintype "passive"))
      (node (ref "R14") (pin "2") (pinfunction "2_2") (pintype "passive"))
    )
    (net (code "35") (name "Net-(C16-Pad1)") (class "Default")
      (node (ref "C16") (pin "1") (pinfunction "1_1") (pintype "passive"))
      (node (ref "C19") (pin "1") (pinfunction "1_1") (pintype "passive"))
      (node (ref "C20") (pin "1") (pinfunction "1_1") (pintype "passive"))
      (node (ref "U$14") (pin "ANT") (pinfunction "ANT_ANT") (pintype "passive"))
    )
    (net (code "36") (name "Net-(C17-Pad1)") (class "Default")
      (node (ref "C17") (pin "1") (pinfunction "1_1") (pintype "passive"))
      (node (ref "R13") (pin "1") (pinfunction "1_1") (pintype "passive"))
    )
    (net (code "37") (name "Net-(CT1-Pad1)") (class "Default")
      (node (ref "CT1") (pin "1") (pinfunction "1_1") (pintype "passive"))
      (node (ref "R19") (pin "1") (pinfunction "1_1") (pintype "passive"))
      (node (ref "R5") (pin "2") (pinfunction "2_2") (pintype "passive"))
      (node (ref "R7") (pin "2") (pinfunction "2_2") (pintype "passive"))
    )
    (net (code "38") (name "Net-(CT2-Pad1)") (class "Default")
      (node (ref "CT2") (pin "1") (pinfunction "1_1") (pintype "passive"))
      (node (ref "R20") (pin "1") (pinfunction "1_1") (pintype "passive"))
      (node (ref "R3") (pin "2") (pinfunction "2_2") (pintype "passive"))
      (node (ref "R8") (pin "2") (pinfunction "2_2") (pintype "passive"))
    )
    (net (code "39") (name "Net-(CT3-Pad1)") (class "Default")
      (node (ref "CT3") (pin "1") (pinfunction "1_1") (pintype "passive"))
      (node (ref "R22") (pin "2") (pinfunction "2_2") (pintype "passive"))
      (node (ref "R25") (pin "1") (pinfunction "1_1") (pintype "passive"))
      (node (ref "R9") (pin "2") (pinfunction "2_2") (pintype "passive"))
    )
    (net (code "40") (name "Net-(CT4-Pad1)") (class "Default")
      (node (ref "CT4") (pin "1") (pinfunction "1_1") (pintype "passive"))
      (node (ref "R16") (pin "2") (pinfunction "2_2") (pintype "passive"))
      (node (ref "R18") (pin "2") (pinfunction "2_2") (pintype "passive"))
      (node (ref "R26") (pin "1") (pinfunction "1_1") (pintype "passive"))
    )
    (net (code "41") (name "Net-(D1-C)") (class "Default")
      (node (ref "D1") (pin "1") (pinfunction "C_1") (pintype "passive"))
      (node (ref "R29") (pin "1") (pinfunction "1_1") (pintype "passive"))
    )
    (net (code "42") (name "Net-(J$1-SIGNAL)") (class "Default")
      (node (ref "C19") (pin "2") (pinfunction "2_2") (pintype "passive"))
      (node (ref "J$1") (pin "SIG") (pinfunction "SIGNAL_SIG") (pintype "bidirectional"))
    )
    (net (code "43") (name "Net-(JP1-1)") (class "Default")
      (node (ref "C2") (pin "2") (pinfunction "2_2") (pintype "passive"))
      (node (ref "JP1") (pin "DTR") (pinfunction "1_DTR") (pintype "passive"))
    )
    (net (code "44") (name "Net-(LED1-PadA)") (class "Default")
      (node (ref "LED1") (pin "A") (pinfunction "A_A") (pintype "passive"))
      (node (ref "R10") (pin "1") (pinfunction "1_1") (pintype "passive"))
    )
    (net (code "45") (name "Net-(R13-Pad2)") (class "Default")
      (node (ref "R13") (pin "2") (pinfunction "2_2") (pintype "passive"))
      (node (ref "R14") (pin "1") (pinfunction "1_1") (pintype "passive"))
      (node (ref "R28") (pin "2") (pinfunction "2_2") (pintype "passive"))
    )
    (net (code "46") (name "Net-(U$11-VIN)") (class "Default")
      (node (ref "C18") (pin "+") (pinfunction "+_+") (pintype "passive"))
      (node (ref "R29") (pin "2") (pinfunction "2_2") (pintype "passive"))
      (node (ref "U$11") (pin "1") (pinfunction "VIN_1") (pintype "input"))
    )
    (net (code "47") (name "Net-(U$11-VOUT)") (class "Default")
      (node (ref "JP2") (pin "1") (pinfunction "1_1") (pintype "passive"))
      (node (ref "U$11") (pin "3") (pinfunction "VOUT_3") (pintype "output"))
    )
    (net (code "48") (name "Net-(U1-AREF)") (class "Default")
      (node (ref "C8") (pin "1") (pinfunction "1_1") (pintype "passive"))
      (node (ref "U1") (pin "20") (pinfunction "AREF_20") (pintype "bidirectional"))
      (node (ref "U1_TQFP") (pin "20") (pinfunction "AREF_20") (pintype "bidirectional"))
    )
    (net (code "49") (name "Net-(U1-PB6(XTAL1{slash}TOSC1))") (class "Default")
      (node (ref "C4") (pin "1") (pinfunction "1_1") (pintype "passive"))
      (node (ref "Q1") (pin "2") (pinfunction "2_2") (pintype "passive"))
      (node (ref "U1") (pin "7") (pinfunction "PB6(XTAL1/TOSC1)_7") (pintype "bidirectional"))
      (node (ref "U1_TQFP") (pin "7") (pinfunction "PB6(XTAL1/TOSC1)_7") (pintype "bidirectional"))
    )
    (net (code "50") (name "Net-(U1-PB7(XTAL2{slash}TOSC2))") (class "Default")
      (node (ref "C11") (pin "1") (pinfunction "1_1") (pintype "passive"))
      (node (ref "Q1") (pin "1") (pinfunction "1_1") (pintype "passive"))
      (node (ref "U1") (pin "8") (pinfunction "PB7(XTAL2/TOSC2)_8") (pintype "bidirectional"))
      (node (ref "U1_TQFP") (pin "8") (pinfunction "PB7(XTAL2/TOSC2)_8") (pintype "bidirectional"))
    )
    (net (code "51") (name "RESET") (class "Default")
      (node (ref "C2") (pin "1") (pinfunction "1_1") (pintype "passive"))
      (node (ref "ISP1") (pin "5") (pinfunction "5_5") (pintype "passive"))
      (node (ref "R32") (pin "1") (pinfunction "1_1") (pintype "passive"))
      (node (ref "S1") (pin "2") (pinfunction "S_2") (pintype "passive"))
      (node (ref "U1") (pin "29") (pinfunction "PC6(/RESET)_29") (pintype "bidirectional"))
      (node (ref "U1_TQFP") (pin "29") (pinfunction "PC6(/RESET)_29") (pintype "bidirectional"))
    )
    (net (code "52") (name "unconnected-(CT1-Pad2)") (class "Default")
      (node (ref "CT1") (pin "2") (pinfunction "2_2") (pintype "passive"))
    )
    (net (code "53") (name "unconnected-(CT1-Pad3)") (class "Default")
      (node (ref "CT1") (pin "3") (pinfunction "3_3") (pintype "passive"))
    )
    (net (code "54") (name "unconnected-(CT2-Pad2)") (class "Default")
      (node (ref "CT2") (pin "2") (pinfunction "2_2") (pintype "passive"))
    )
    (net (code "55") (name "unconnected-(CT2-Pad3)") (class "Default")
      (node (ref "CT2") (pin "3") (pinfunction "3_3") (pintype "passive"))
    )
    (net (code "56") (name "unconnected-(CT3-Pad2)") (class "Default")
      (node (ref "CT3") (pin "2") (pinfunction "2_2") (pintype "passive"))
    )
    (net (code "57") (name "unconnected-(CT3-Pad3)") (class "Default")
      (node (ref "CT3") (pin "3") (pinfunction "3_3") (pintype "passive"))
    )
    (net (code "58") (name "unconnected-(CT4-Pad2)") (class "Default")
      (node (ref "CT4") (pin "2") (pinfunction "2_2") (pintype "passive"))
    )
    (net (code "59") (name "unconnected-(CT4-Pad3)") (class "Default")
      (node (ref "CT4") (pin "3") (pinfunction "3_3") (pintype "passive"))
    )
    (net (code "60") (name "unconnected-(JP1-5-PadCTS)") (class "Default")
      (node (ref "JP1") (pin "CTS") (pinfunction "5_CTS") (pintype "passive"))
    )
    (net (code "61") (name "unconnected-(U$10-PadD+)") (class "Default")
      (node (ref "U$10") (pin "D+") (pinfunction "D+_D+") (pintype "bidirectional"))
    )
    (net (code "62") (name "unconnected-(U$10-PadD-)") (class "Default")
      (node (ref "U$10") (pin "D-") (pinfunction "D-_D-") (pintype "bidirectional"))
    )
    (net (code "63") (name "unconnected-(U$10-PadID)") (class "Default")
      (node (ref "U$10") (pin "ID") (pinfunction "ID_ID") (pintype "bidirectional"))
    )
    (net (code "64") (name "unconnected-(U$14-PadFFS)") (class "Default")
      (node (ref "U$14") (pin "FFS") (pinfunction "FFS_FFS") (pintype "bidirectional"))
    )
  )
)
